# MezzanineDCDC_8033.net
KiCad netlist of a schematic drawn in Altium Designer
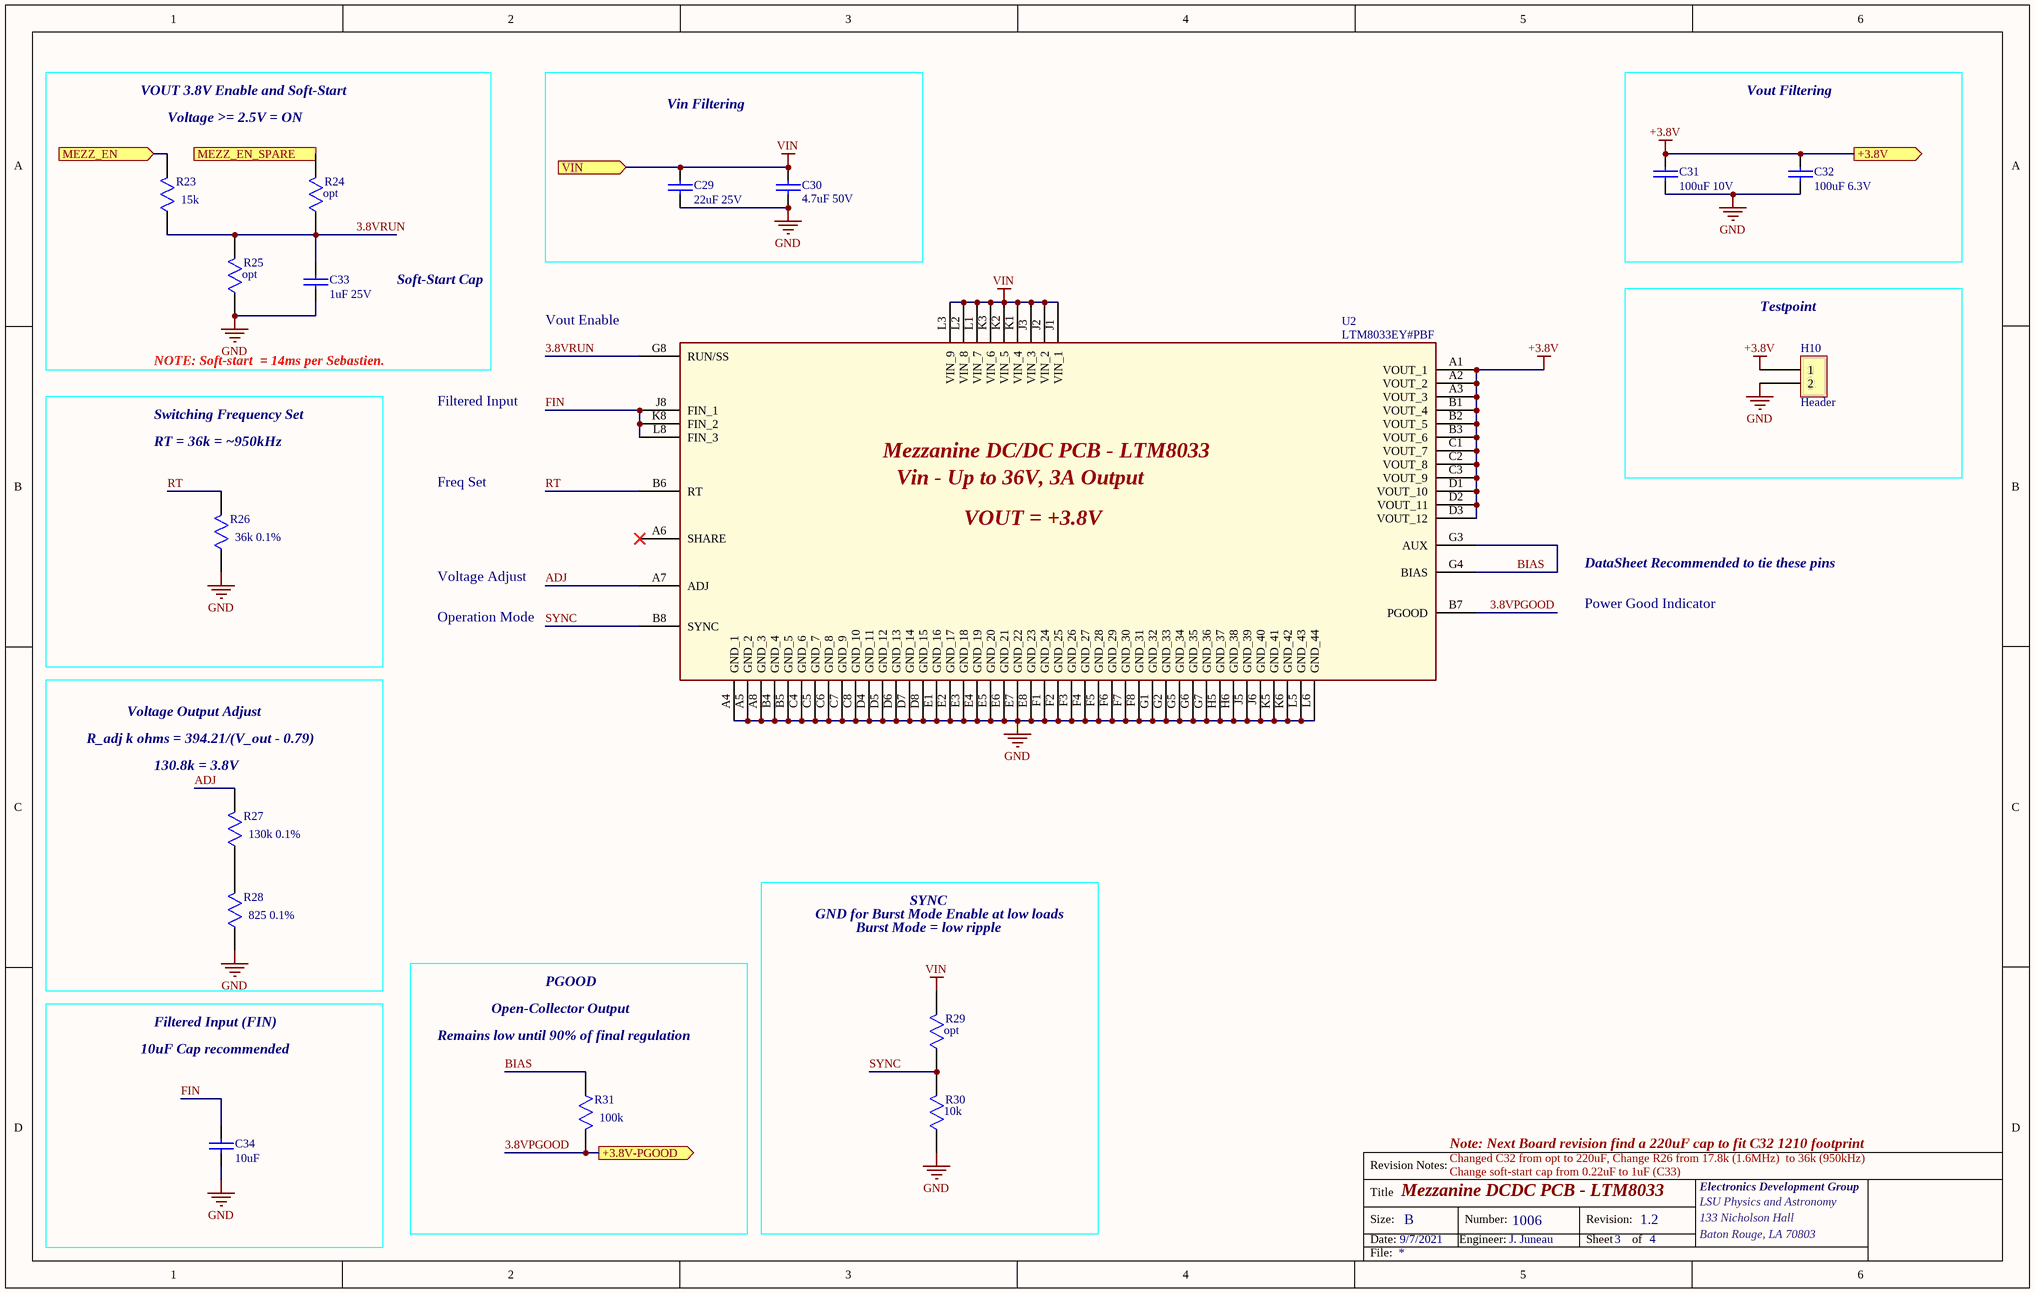
[diagram p0: MezzanineDCDC_8033.SchDoc]

(export (version "E")
  (design (tool "Eeschema 10.0.6"))
  (components
    (comp (ref "C29")
      (value "22uF 25V")
      (footprint "CAP 1210 Murata")
      (description "22µF ±10% 25V Ceramic Capacitor X5R 1210 (3225 Metric)")
      (fields (field (name "Comment") "GRM32ER61E226KE15L"))
      (libsource (lib "MezzanineDCDC") (part "Capacitor 1210"))
    )
    (comp (ref "C30")
      (value "4.7uF 50V")
      (footprint "CAP 1206 TDK")
      (description "4.7µF ±10% 50V Ceramic Capacitor X5R 1206 (3216 Metric)")
      (fields (field (name "Comment") "UMK316BJ475KL-T"))
      (libsource (lib "MezzanineDCDC") (part "Capacitor 1206"))
    )
    (comp (ref "C31")
      (value "100uF 10V")
      (footprint "CAP 1210 Murata")
      (description "CAP CER 100UF 10V X5R 1210")
      (fields (field (name "Comment") "LMK325BJ107MM-T"))
      (libsource (lib "MezzanineDCDC") (part "Capacitor 1210"))
    )
    (comp (ref "C32")
      (value "100uF 6.3V")
      (footprint "CAP 1210 Murata")
      (description "220 µF ±20% 6.3V Ceramic Capacitor X5R 1206 (3216 Metric)")
      (fields (field (name "Comment") "GRM31CR60J227ME11L"))
      (libsource (lib "MezzanineDCDC") (part "Capacitor 1210"))
    )
    (comp (ref "C33")
      (value "1uF 25V")
      (footprint "Cap 0603 TDK")
      (description "1 µF ±10% 25V Ceramic Capacitor X7R 0603 (1608 Metric)")
      (fields (field (name "Comment") "06033C105KAT4A"))
      (libsource (lib "MezzanineDCDC") (part "Capacitor 0603 TDK"))
    )
    (comp (ref "C34")
      (value "10uF")
      (footprint "CAP 1210 Murata")
      (description "CAP CER 10UF 50V X7R 1210")
      (fields (field (name "Comment") "GRM32ER71H106KA12L"))
      (libsource (lib "MezzanineDCDC") (part "Capacitor 1210"))
    )
    (comp (ref "H10")
      (value "Header")
      (footprint "Header 2Pin")
      (description "Connector Header Through Hole 2 position 0.100\" (2.54mm)")
      (libsource (lib "MezzanineDCDC") (part "Header - 2Pin"))
    )
    (comp (ref "R23")
      (value "15k")
      (footprint "Resistor ERJ2G/CRCW 0402")
      (description "RES 15K OHM 1% 1/10W 0402 SMD")
      (fields (field (name "Comment") "ERJ-U02F1502X"))
      (libsource (lib "MezzanineDCDC") (part "ERJ2G Resistor 0402"))
    )
    (comp (ref "R24")
      (value "opt")
      (footprint "Resistor ERJ2G/CRCW 0402")
      (description "Resistor 0402")
      (libsource (lib "MezzanineDCDC") (part "ERJ2G Resistor 0402"))
    )
    (comp (ref "R25")
      (value "opt")
      (footprint "Resistor ERJ2G/CRCW 0402")
      (description "Resistor 0402")
      (libsource (lib "MezzanineDCDC") (part "ERJ2G Resistor 0402"))
    )
    (comp (ref "R26")
      (value "36k 0.1%")
      (footprint "Resistor 0603 - ERJ")
      (description "36 kOhms ±0.1% 0.1W, 1/10W Chip Resistor 0603 (1608 Metric) Automotive AEC-Q200 Thin Film")
      (fields (field (name "Comment") "ERA-3APB363V"))
      (libsource (lib "MezzanineDCDC") (part "Resistor 0603"))
    )
    (comp (ref "R27")
      (value "130k 0.1%")
      (footprint "Resistor 0603 - ERJ")
      (description "RES SMD 130K OHM 0.1% 1/10W 0603")
      (fields (field (name "Comment") "ERA-3AEB134V"))
      (libsource (lib "MezzanineDCDC") (part "Resistor 0603"))
    )
    (comp (ref "R28")
      (value "825 0.1%")
      (footprint "Resistor 0603 - ERJ")
      (description "RES SMD 825 OHM 0.1% 1/10W 0603")
      (fields (field (name "Comment") "ERA-3AEB8250V"))
      (libsource (lib "MezzanineDCDC") (part "Resistor 0603"))
    )
    (comp (ref "R29")
      (value "opt")
      (footprint "Resistor ERJ2G/CRCW 0402")
      (description "Resistor 0402")
      (libsource (lib "MezzanineDCDC") (part "ERJ2G Resistor 0402"))
    )
    (comp (ref "R30")
      (value "10k")
      (footprint "Resistor ERJ2G/CRCW 0402")
      (description "RES SMD 10K OHM 5% 1/10W 0402")
      (fields (field (name "Comment") "ERJ-2GEJ103X"))
      (libsource (lib "MezzanineDCDC") (part "ERJ2G Resistor 0402"))
    )
    (comp (ref "R31")
      (value "100k")
      (footprint "Resistor ERJ2G/CRCW 0402")
      (description "RES SMD 100K OHM 1% 1/10W 0402")
      (fields (field (name "Comment") "ERJ-2RKF1003X"))
      (libsource (lib "MezzanineDCDC") (part "ERJ2G Resistor 0402"))
    )
    (comp (ref "U2")
      (value "LTM8033EY#PBF")
      (footprint "LTM8033 BGA")
      (description "Non-Isolated PoL Module DC DC Converter Output 0.8 ~ 24V - - 3A 3.6V - 36V Input")
      (libsource (lib "MezzanineDCDC") (part "LTM8033"))
    )
  )
  (nets
    (net (code "1") (name "+3.8V") (class "Default")
      (node (ref "C31") (pin "1") (pinfunction "1_1") (pintype "passive"))
      (node (ref "C32") (pin "1") (pinfunction "1_1") (pintype "passive"))
      (node (ref "H10") (pin "1") (pinfunction "1_1") (pintype "passive"))
      (node (ref "U2") (pin "A1") (pinfunction "VOUT_1_A1") (pintype "passive"))
      (node (ref "U2") (pin "A2") (pinfunction "VOUT_2_A2") (pintype "passive"))
      (node (ref "U2") (pin "A3") (pinfunction "VOUT_3_A3") (pintype "passive"))
      (node (ref "U2") (pin "B1") (pinfunction "VOUT_4_B1") (pintype "passive"))
      (node (ref "U2") (pin "B2") (pinfunction "VOUT_5_B2") (pintype "passive"))
      (node (ref "U2") (pin "B3") (pinfunction "VOUT_6_B3") (pintype "passive"))
      (node (ref "U2") (pin "C1") (pinfunction "VOUT_7_C1") (pintype "passive"))
      (node (ref "U2") (pin "C2") (pinfunction "VOUT_8_C2") (pintype "passive"))
      (node (ref "U2") (pin "C3") (pinfunction "VOUT_9_C3") (pintype "passive"))
      (node (ref "U2") (pin "D1") (pinfunction "VOUT_10_D1") (pintype "passive"))
      (node (ref "U2") (pin "D2") (pinfunction "VOUT_11_D2") (pintype "passive"))
      (node (ref "U2") (pin "D3") (pinfunction "VOUT_12_D3") (pintype "passive"))
    )
    (net (code "2") (name "/3.8VPGOOD") (class "Default")
      (node (ref "R31") (pin "2") (pinfunction "1_2") (pintype "passive"))
      (node (ref "U2") (pin "B7") (pinfunction "PGOOD_B7") (pintype "passive"))
    )
    (net (code "3") (name "/3.8VRUN") (class "Default")
      (node (ref "C33") (pin "1") (pinfunction "1_1") (pintype "passive"))
      (node (ref "R23") (pin "1") (pinfunction "0_1") (pintype "passive"))
      (node (ref "R24") (pin "1") (pinfunction "0_1") (pintype "passive"))
      (node (ref "R25") (pin "2") (pinfunction "1_2") (pintype "passive"))
      (node (ref "U2") (pin "G8") (pinfunction "RUN/SS_G8") (pintype "passive"))
    )
    (net (code "4") (name "/ADJ") (class "Default")
      (node (ref "R27") (pin "2") (pinfunction "1_2") (pintype "passive"))
      (node (ref "U2") (pin "A7") (pinfunction "ADJ_A7") (pintype "passive"))
    )
    (net (code "5") (name "/BIAS") (class "Default")
      (node (ref "R31") (pin "1") (pinfunction "0_1") (pintype "passive"))
      (node (ref "U2") (pin "G3") (pinfunction "AUX_G3") (pintype "passive"))
      (node (ref "U2") (pin "G4") (pinfunction "BIAS_G4") (pintype "passive"))
    )
    (net (code "6") (name "/FIN") (class "Default")
      (node (ref "C34") (pin "1") (pinfunction "1_1") (pintype "passive"))
      (node (ref "U2") (pin "J8") (pinfunction "FIN_1_J8") (pintype "passive"))
      (node (ref "U2") (pin "K8") (pinfunction "FIN_2_K8") (pintype "passive"))
      (node (ref "U2") (pin "L8") (pinfunction "FIN_3_L8") (pintype "passive"))
    )
    (net (code "7") (name "/MEZZ_EN") (class "Default")
      (node (ref "R23") (pin "2") (pinfunction "1_2") (pintype "passive"))
    )
    (net (code "8") (name "/MEZZ_EN_SPARE") (class "Default")
      (node (ref "R24") (pin "2") (pinfunction "1_2") (pintype "passive"))
    )
    (net (code "9") (name "/RT") (class "Default")
      (node (ref "R26") (pin "2") (pinfunction "1_2") (pintype "passive"))
      (node (ref "U2") (pin "B6") (pinfunction "RT_B6") (pintype "passive"))
    )
    (net (code "10") (name "/SYNC") (class "Default")
      (node (ref "R29") (pin "1") (pinfunction "0_1") (pintype "passive"))
      (node (ref "R30") (pin "2") (pinfunction "1_2") (pintype "passive"))
      (node (ref "U2") (pin "B8") (pinfunction "SYNC_B8") (pintype "passive"))
    )
    (net (code "11") (name "GND") (class "Default")
      (node (ref "C29") (pin "2") (pinfunction "2_2") (pintype "passive"))
      (node (ref "C30") (pin "2") (pinfunction "2_2") (pintype "passive"))
      (node (ref "C31") (pin "2") (pinfunction "2_2") (pintype "passive"))
      (node (ref "C32") (pin "2") (pinfunction "2_2") (pintype "passive"))
      (node (ref "C33") (pin "2") (pinfunction "2_2") (pintype "passive"))
      (node (ref "C34") (pin "2") (pinfunction "2_2") (pintype "passive"))
      (node (ref "H10") (pin "2") (pinfunction "2_2") (pintype "passive"))
      (node (ref "R25") (pin "1") (pinfunction "0_1") (pintype "passive"))
      (node (ref "R26") (pin "1") (pinfunction "0_1") (pintype "passive"))
      (node (ref "R28") (pin "1") (pinfunction "0_1") (pintype "passive"))
      (node (ref "R30") (pin "1") (pinfunction "0_1") (pintype "passive"))
      (node (ref "U2") (pin "A4") (pinfunction "GND_1_A4") (pintype "passive"))
      (node (ref "U2") (pin "A5") (pinfunction "GND_2_A5") (pintype "passive"))
      (node (ref "U2") (pin "A8") (pinfunction "GND_3_A8") (pintype "passive"))
      (node (ref "U2") (pin "B4") (pinfunction "GND_4_B4") (pintype "passive"))
      (node (ref "U2") (pin "B5") (pinfunction "GND_5_B5") (pintype "passive"))
      (node (ref "U2") (pin "C4") (pinfunction "GND_6_C4") (pintype "passive"))
      (node (ref "U2") (pin "C5") (pinfunction "GND_7_C5") (pintype "passive"))
      (node (ref "U2") (pin "C6") (pinfunction "GND_8_C6") (pintype "passive"))
      (node (ref "U2") (pin "C7") (pinfunction "GND_9_C7") (pintype "passive"))
      (node (ref "U2") (pin "C8") (pinfunction "GND_10_C8") (pintype "passive"))
      (node (ref "U2") (pin "D4") (pinfunction "GND_11_D4") (pintype "passive"))
      (node (ref "U2") (pin "D5") (pinfunction "GND_12_D5") (pintype "passive"))
      (node (ref "U2") (pin "D6") (pinfunction "GND_13_D6") (pintype "passive"))
      (node (ref "U2") (pin "D7") (pinfunction "GND_14_D7") (pintype "passive"))
      (node (ref "U2") (pin "D8") (pinfunction "GND_15_D8") (pintype "passive"))
      (node (ref "U2") (pin "E1") (pinfunction "GND_16_E1") (pintype "passive"))
      (node (ref "U2") (pin "E2") (pinfunction "GND_17_E2") (pintype "passive"))
      (node (ref "U2") (pin "E3") (pinfunction "GND_18_E3") (pintype "passive"))
      (node (ref "U2") (pin "E4") (pinfunction "GND_19_E4") (pintype "passive"))
      (node (ref "U2") (pin "E5") (pinfunction "GND_20_E5") (pintype "passive"))
      (node (ref "U2") (pin "E6") (pinfunction "GND_21_E6") (pintype "passive"))
      (node (ref "U2") (pin "E7") (pinfunction "GND_22_E7") (pintype "passive"))
      (node (ref "U2") (pin "E8") (pinfunction "GND_23_E8") (pintype "passive"))
      (node (ref "U2") (pin "F1") (pinfunction "GND_24_F1") (pintype "passive"))
      (node (ref "U2") (pin "F2") (pinfunction "GND_25_F2") (pintype "passive"))
      (node (ref "U2") (pin "F3") (pinfunction "GND_26_F3") (pintype "passive"))
      (node (ref "U2") (pin "F4") (pinfunction "GND_27_F4") (pintype "passive"))
      (node (ref "U2") (pin "F5") (pinfunction "GND_28_F5") (pintype "passive"))
      (node (ref "U2") (pin "F6") (pinfunction "GND_29_F6") (pintype "passive"))
      (node (ref "U2") (pin "F7") (pinfunction "GND_30_F7") (pintype "passive"))
      (node (ref "U2") (pin "F8") (pinfunction "GND_31_F8") (pintype "passive"))
      (node (ref "U2") (pin "G1") (pinfunction "GND_32_G1") (pintype "passive"))
      (node (ref "U2") (pin "G2") (pinfunction "GND_33_G2") (pintype "passive"))
      (node (ref "U2") (pin "G5") (pinfunction "GND_34_G5") (pintype "passive"))
      (node (ref "U2") (pin "G6") (pinfunction "GND_35_G6") (pintype "passive"))
      (node (ref "U2") (pin "G7") (pinfunction "GND_36_G7") (pintype "passive"))
      (node (ref "U2") (pin "H5") (pinfunction "GND_37_H5") (pintype "passive"))
      (node (ref "U2") (pin "H6") (pinfunction "GND_38_H6") (pintype "passive"))
      (node (ref "U2") (pin "J5") (pinfunction "GND_39_J5") (pintype "passive"))
      (node (ref "U2") (pin "J6") (pinfunction "GND_40_J6") (pintype "passive"))
      (node (ref "U2") (pin "K5") (pinfunction "GND_41_K5") (pintype "passive"))
      (node (ref "U2") (pin "K6") (pinfunction "GND_42_K6") (pintype "passive"))
      (node (ref "U2") (pin "L5") (pinfunction "GND_43_L5") (pintype "passive"))
      (node (ref "U2") (pin "L6") (pinfunction "GND_44_L6") (pintype "passive"))
    )
    (net (code "12") (name "Net-(R27-0)") (class "Default")
      (node (ref "R27") (pin "1") (pinfunction "0_1") (pintype "passive"))
      (node (ref "R28") (pin "2") (pinfunction "1_2") (pintype "passive"))
    )
    (net (code "13") (name "VIN") (class "Default")
      (node (ref "C29") (pin "1") (pinfunction "1_1") (pintype "passive"))
      (node (ref "C30") (pin "1") (pinfunction "1_1") (pintype "passive"))
      (node (ref "R29") (pin "2") (pinfunction "1_2") (pintype "passive"))
      (node (ref "U2") (pin "J1") (pinfunction "VIN_1_J1") (pintype "passive"))
      (node (ref "U2") (pin "J2") (pinfunction "VIN_2_J2") (pintype "passive"))
      (node (ref "U2") (pin "J3") (pinfunction "VIN_3_J3") (pintype "passive"))
      (node (ref "U2") (pin "K1") (pinfunction "VIN_4_K1") (pintype "passive"))
      (node (ref "U2") (pin "K2") (pinfunction "VIN_5_K2") (pintype "passive"))
      (node (ref "U2") (pin "K3") (pinfunction "VIN_6_K3") (pintype "passive"))
      (node (ref "U2") (pin "L1") (pinfunction "VIN_7_L1") (pintype "passive"))
      (node (ref "U2") (pin "L2") (pinfunction "VIN_8_L2") (pintype "passive"))
      (node (ref "U2") (pin "L3") (pinfunction "VIN_9_L3") (pintype "passive"))
    )
    (net (code "14") (name "unconnected-(U2-SHARE-PadA6)") (class "Default")
      (node (ref "U2") (pin "A6") (pinfunction "SHARE_A6") (pintype "passive+no_connect"))
    )
  )
)
